# main.net
KiCad netlist of a schematic drawn in EAGLE
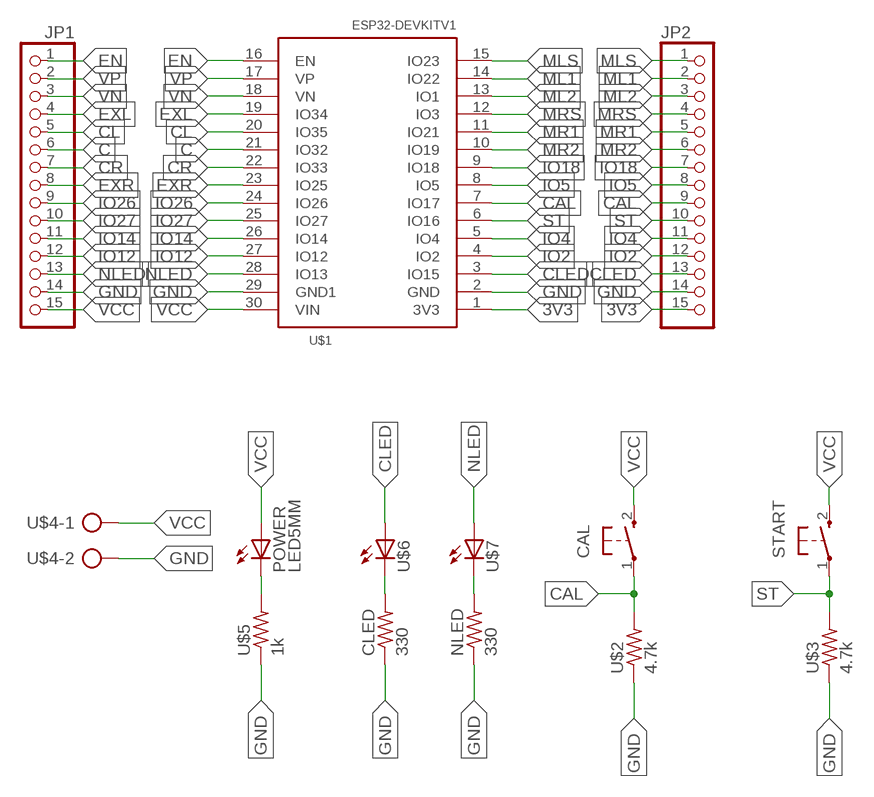
[diagram p0: schematic, sheet 1]

(export (version "E")
  (design (tool "Eeschema 10.0.6"))
  (components
    (comp (ref "CAL")
      (value "PUSH_BUTTON")
      (footprint "eagle-import:B3F-10XX")
      (libsource (lib "eagle-import") (part "PUSH_BUTTON"))
    )
    (comp (ref "CLED")
      (value "330")
      (footprint "eagle-import:0204_7")
      (libsource (lib "eagle-import") (part "RES-7"))
    )
    (comp (ref "JP1")
      (value "PINHD-1X15")
      (footprint "eagle-import:1X15")
      (libsource (lib "eagle-import") (part "PINHD-1X15"))
    )
    (comp (ref "JP2")
      (value "PINHD-1X15")
      (footprint "eagle-import:1X15")
      (libsource (lib "eagle-import") (part "PINHD-1X15"))
    )
    (comp (ref "NLED")
      (value "330")
      (footprint "eagle-import:0204_7")
      (libsource (lib "eagle-import") (part "RES-7"))
    )
    (comp (ref "POWER")
      (value "LED5MM")
      (footprint "eagle-import:LED5MM")
      (libsource (lib "eagle-import") (part "LED5MM"))
    )
    (comp (ref "START")
      (value "PUSH_BUTTON")
      (footprint "eagle-import:B3F-10XX")
      (libsource (lib "eagle-import") (part "PUSH_BUTTON"))
    )
    (comp (ref "U$1")
      (value "ESP32DEVKITV1")
      (footprint "eagle-import:ESP32-DEVKITV1")
      (libsource (lib "eagle-import") (part "ESP32DEVKITV1"))
    )
    (comp (ref "U$2")
      (value "4.7k")
      (footprint "eagle-import:0204_7")
      (libsource (lib "eagle-import") (part "RES-7"))
    )
    (comp (ref "U$3")
      (value "4.7k")
      (footprint "eagle-import:0204_7")
      (libsource (lib "eagle-import") (part "RES-7"))
    )
    (comp (ref "U$4")
      (value "CON_PTR_2(V_2)")
      (footprint "eagle-import:AK300_2")
      (libsource (lib "eagle-import") (part "CON_PTR_2(V_2)"))
    )
    (comp (ref "U$5")
      (value "1k")
      (footprint "eagle-import:0204_7")
      (libsource (lib "eagle-import") (part "RES-7"))
    )
    (comp (ref "U$6")
      (value "LED5MM")
      (footprint "eagle-import:LED5MM")
      (libsource (lib "eagle-import") (part "LED5MM"))
    )
    (comp (ref "U$7")
      (value "LED5MM")
      (footprint "eagle-import:LED5MM")
      (libsource (lib "eagle-import") (part "LED5MM"))
    )
  )
  (nets
    (net (code "1") (name "3V3") (class "Default")
      (node (ref "JP2") (pin "15") (pinfunction "15_15") (pintype "passive"))
      (node (ref "U$1") (pin "1") (pinfunction "3V3_1") (pintype "bidirectional"))
    )
    (net (code "2") (name "C") (class "Default")
      (node (ref "JP1") (pin "6") (pinfunction "6_6") (pintype "passive"))
      (node (ref "U$1") (pin "21") (pinfunction "IO32_21") (pintype "bidirectional"))
    )
    (net (code "3") (name "CAL") (class "Default")
      (node (ref "CAL") (pin "1") (pinfunction "P_1") (pintype "passive"))
      (node (ref "JP2") (pin "9") (pinfunction "9_9") (pintype "passive"))
      (node (ref "U$1") (pin "7") (pinfunction "IO17_7") (pintype "bidirectional"))
      (node (ref "U$2") (pin "2") (pinfunction "2_2") (pintype "passive"))
    )
    (net (code "4") (name "CL") (class "Default")
      (node (ref "JP1") (pin "5") (pinfunction "5_5") (pintype "passive"))
      (node (ref "U$1") (pin "20") (pinfunction "IO35_20") (pintype "bidirectional"))
    )
    (net (code "5") (name "CLED") (class "Default")
      (node (ref "JP2") (pin "13") (pinfunction "13_13") (pintype "passive"))
      (node (ref "U$1") (pin "3") (pinfunction "IO15_3") (pintype "bidirectional"))
      (node (ref "U$6") (pin "A") (pinfunction "A_A") (pintype "passive"))
    )
    (net (code "6") (name "CR") (class "Default")
      (node (ref "JP1") (pin "7") (pinfunction "7_7") (pintype "passive"))
      (node (ref "U$1") (pin "22") (pinfunction "IO33_22") (pintype "bidirectional"))
    )
    (net (code "7") (name "EN") (class "Default")
      (node (ref "JP1") (pin "1") (pinfunction "1_1") (pintype "passive"))
      (node (ref "U$1") (pin "16") (pinfunction "EN_16") (pintype "bidirectional"))
    )
    (net (code "8") (name "EXL") (class "Default")
      (node (ref "JP1") (pin "4") (pinfunction "4_4") (pintype "passive"))
      (node (ref "U$1") (pin "19") (pinfunction "IO34_19") (pintype "bidirectional"))
    )
    (net (code "9") (name "EXR") (class "Default")
      (node (ref "JP1") (pin "8") (pinfunction "8_8") (pintype "passive"))
      (node (ref "U$1") (pin "23") (pinfunction "IO25_23") (pintype "bidirectional"))
    )
    (net (code "10") (name "GND") (class "Default")
      (node (ref "CLED") (pin "1") (pinfunction "1_1") (pintype "passive"))
      (node (ref "JP1") (pin "14") (pinfunction "14_14") (pintype "passive"))
      (node (ref "JP2") (pin "14") (pinfunction "14_14") (pintype "passive"))
      (node (ref "NLED") (pin "1") (pinfunction "1_1") (pintype "passive"))
      (node (ref "U$1") (pin "2") (pinfunction "GND_2") (pintype "bidirectional"))
      (node (ref "U$1") (pin "29") (pinfunction "GND1_29") (pintype "bidirectional"))
      (node (ref "U$2") (pin "1") (pinfunction "1_1") (pintype "passive"))
      (node (ref "U$3") (pin "1") (pinfunction "1_1") (pintype "passive"))
      (node (ref "U$4") (pin "2") (pinfunction "KL_2") (pintype "passive"))
      (node (ref "U$5") (pin "1") (pinfunction "1_1") (pintype "passive"))
    )
    (net (code "11") (name "IO2") (class "Default")
      (node (ref "JP2") (pin "12") (pinfunction "12_12") (pintype "passive"))
      (node (ref "U$1") (pin "4") (pinfunction "IO2_4") (pintype "bidirectional"))
    )
    (net (code "12") (name "IO4") (class "Default")
      (node (ref "JP2") (pin "11") (pinfunction "11_11") (pintype "passive"))
      (node (ref "U$1") (pin "5") (pinfunction "IO4_5") (pintype "bidirectional"))
    )
    (net (code "13") (name "IO5") (class "Default")
      (node (ref "JP2") (pin "8") (pinfunction "8_8") (pintype "passive"))
      (node (ref "U$1") (pin "8") (pinfunction "IO5_8") (pintype "bidirectional"))
    )
    (net (code "14") (name "IO12") (class "Default")
      (node (ref "JP1") (pin "12") (pinfunction "12_12") (pintype "passive"))
      (node (ref "U$1") (pin "27") (pinfunction "IO12_27") (pintype "bidirectional"))
    )
    (net (code "15") (name "IO14") (class "Default")
      (node (ref "JP1") (pin "11") (pinfunction "11_11") (pintype "passive"))
      (node (ref "U$1") (pin "26") (pinfunction "IO14_26") (pintype "bidirectional"))
    )
    (net (code "16") (name "IO18") (class "Default")
      (node (ref "JP2") (pin "7") (pinfunction "7_7") (pintype "passive"))
      (node (ref "U$1") (pin "9") (pinfunction "IO18_9") (pintype "bidirectional"))
    )
    (net (code "17") (name "IO26") (class "Default")
      (node (ref "JP1") (pin "9") (pinfunction "9_9") (pintype "passive"))
      (node (ref "U$1") (pin "24") (pinfunction "IO26_24") (pintype "bidirectional"))
    )
    (net (code "18") (name "IO27") (class "Default")
      (node (ref "JP1") (pin "10") (pinfunction "10_10") (pintype "passive"))
      (node (ref "U$1") (pin "25") (pinfunction "IO27_25") (pintype "bidirectional"))
    )
    (net (code "19") (name "ML1") (class "Default")
      (node (ref "JP2") (pin "2") (pinfunction "2_2") (pintype "passive"))
      (node (ref "U$1") (pin "14") (pinfunction "IO22_14") (pintype "bidirectional"))
    )
    (net (code "20") (name "ML2") (class "Default")
      (node (ref "JP2") (pin "3") (pinfunction "3_3") (pintype "passive"))
      (node (ref "U$1") (pin "13") (pinfunction "IO1_13") (pintype "bidirectional"))
    )
    (net (code "21") (name "MLS") (class "Default")
      (node (ref "JP2") (pin "1") (pinfunction "1_1") (pintype "passive"))
      (node (ref "U$1") (pin "15") (pinfunction "IO23_15") (pintype "bidirectional"))
    )
    (net (code "22") (name "MR1") (class "Default")
      (node (ref "JP2") (pin "5") (pinfunction "5_5") (pintype "passive"))
      (node (ref "U$1") (pin "11") (pinfunction "IO21_11") (pintype "bidirectional"))
    )
    (net (code "23") (name "MR2") (class "Default")
      (node (ref "JP2") (pin "6") (pinfunction "6_6") (pintype "passive"))
      (node (ref "U$1") (pin "10") (pinfunction "IO19_10") (pintype "bidirectional"))
    )
    (net (code "24") (name "MRS") (class "Default")
      (node (ref "JP2") (pin "4") (pinfunction "4_4") (pintype "passive"))
      (node (ref "U$1") (pin "12") (pinfunction "IO3_12") (pintype "bidirectional"))
    )
    (net (code "25") (name "NLED") (class "Default")
      (node (ref "JP1") (pin "13") (pinfunction "13_13") (pintype "passive"))
      (node (ref "U$1") (pin "28") (pinfunction "IO13_28") (pintype "bidirectional"))
      (node (ref "U$7") (pin "A") (pinfunction "A_A") (pintype "passive"))
    )
    (net (code "26") (name "Net-(POWER-C)") (class "Default")
      (node (ref "POWER") (pin "K") (pinfunction "C_K") (pintype "passive"))
      (node (ref "U$5") (pin "2") (pinfunction "2_2") (pintype "passive"))
    )
    (net (code "27") (name "Net-(U$6-C)") (class "Default")
      (node (ref "CLED") (pin "2") (pinfunction "2_2") (pintype "passive"))
      (node (ref "U$6") (pin "K") (pinfunction "C_K") (pintype "passive"))
    )
    (net (code "28") (name "Net-(U$7-C)") (class "Default")
      (node (ref "NLED") (pin "2") (pinfunction "2_2") (pintype "passive"))
      (node (ref "U$7") (pin "K") (pinfunction "C_K") (pintype "passive"))
    )
    (net (code "29") (name "ST") (class "Default")
      (node (ref "JP2") (pin "10") (pinfunction "10_10") (pintype "passive"))
      (node (ref "START") (pin "1") (pinfunction "P_1") (pintype "passive"))
      (node (ref "U$1") (pin "6") (pinfunction "IO16_6") (pintype "bidirectional"))
      (node (ref "U$3") (pin "2") (pinfunction "2_2") (pintype "passive"))
    )
    (net (code "30") (name "VCC") (class "Default")
      (node (ref "CAL") (pin "2") (pinfunction "S_2") (pintype "passive"))
      (node (ref "JP1") (pin "15") (pinfunction "15_15") (pintype "passive"))
      (node (ref "POWER") (pin "A") (pinfunction "A_A") (pintype "passive"))
      (node (ref "START") (pin "2") (pinfunction "S_2") (pintype "passive"))
      (node (ref "U$1") (pin "30") (pinfunction "VIN_30") (pintype "bidirectional"))
      (node (ref "U$4") (pin "1") (pinfunction "KL_1") (pintype "passive"))
    )
    (net (code "31") (name "VN") (class "Default")
      (node (ref "JP1") (pin "3") (pinfunction "3_3") (pintype "passive"))
      (node (ref "U$1") (pin "18") (pinfunction "VN_18") (pintype "bidirectional"))
    )
    (net (code "32") (name "VP") (class "Default")
      (node (ref "JP1") (pin "2") (pinfunction "2_2") (pintype "passive"))
      (node (ref "U$1") (pin "17") (pinfunction "VP_17") (pintype "bidirectional"))
    )
  )
)
